# Bus.net
KiCad netlist of a schematic drawn in Altium Designer
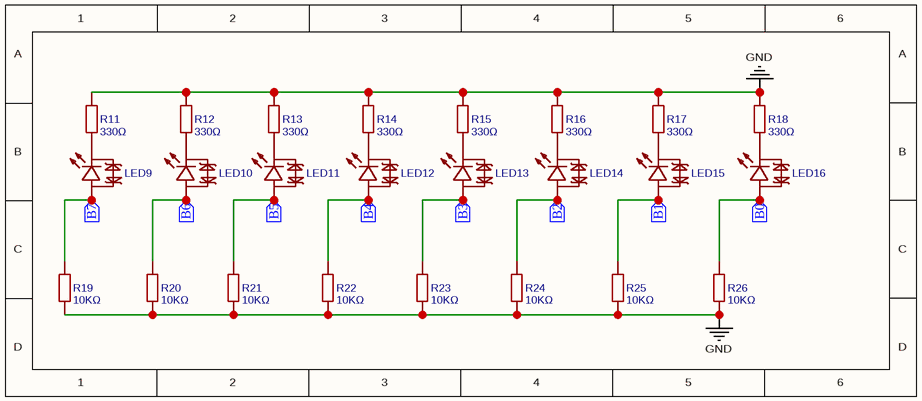
[diagram p0: Bus.schdoc]

(export (version "E")
  (design (tool "Eeschema 10.0.6"))
  (components
    (comp (ref "LED9")
      (value "204-15UTC/S400-X9-L")
      (fields (field (name "MANUFACTURER") "EVERLIGHT(亿光)") (field (name "CONTRIBUTOR") "LCSC"))
      (libsource (lib "altium-import") (part "root_1_204-15UTC/S400-X9-L_"))
    )
    (comp (ref "LED10")
      (value "204-15UTC/S400-X9-L")
      (fields (field (name "MANUFACTURER") "EVERLIGHT(亿光)") (field (name "CONTRIBUTOR") "LCSC"))
      (libsource (lib "altium-import") (part "root_1_204-15UTC/S400-X9-L_"))
    )
    (comp (ref "LED11")
      (value "204-15UTC/S400-X9-L")
      (fields (field (name "MANUFACTURER") "EVERLIGHT(亿光)") (field (name "CONTRIBUTOR") "LCSC"))
      (libsource (lib "altium-import") (part "root_1_204-15UTC/S400-X9-L_"))
    )
    (comp (ref "LED12")
      (value "204-15UTC/S400-X9-L")
      (fields (field (name "MANUFACTURER") "EVERLIGHT(亿光)") (field (name "CONTRIBUTOR") "LCSC"))
      (libsource (lib "altium-import") (part "root_1_204-15UTC/S400-X9-L_"))
    )
    (comp (ref "LED13")
      (value "204-15UTC/S400-X9-L")
      (fields (field (name "MANUFACTURER") "EVERLIGHT(亿光)") (field (name "CONTRIBUTOR") "LCSC"))
      (libsource (lib "altium-import") (part "root_1_204-15UTC/S400-X9-L_"))
    )
    (comp (ref "LED14")
      (value "204-15UTC/S400-X9-L")
      (fields (field (name "MANUFACTURER") "EVERLIGHT(亿光)") (field (name "CONTRIBUTOR") "LCSC"))
      (libsource (lib "altium-import") (part "root_1_204-15UTC/S400-X9-L_"))
    )
    (comp (ref "LED15")
      (value "204-15UTC/S400-X9-L")
      (fields (field (name "MANUFACTURER") "EVERLIGHT(亿光)") (field (name "CONTRIBUTOR") "LCSC"))
      (libsource (lib "altium-import") (part "root_1_204-15UTC/S400-X9-L_"))
    )
    (comp (ref "LED16")
      (value "204-15UTC/S400-X9-L")
      (fields (field (name "MANUFACTURER") "EVERLIGHT(亿光)") (field (name "CONTRIBUTOR") "LCSC"))
      (libsource (lib "altium-import") (part "root_1_204-15UTC/S400-X9-L_"))
    )
    (comp (ref "R11")
      (value "330Ω")
      (fields
        (field (name "MANUFACTURER") "CCO(千志电子)")
        (field (name "MANUFACTURER PART") "MF1/2W-0.1Ω±1% T")
        (field (name "CONTRIBUTOR") "LCSC")
      )
      (libsource (lib "altium-import") (part "root_1_330Ω_"))
    )
    (comp (ref "R12")
      (value "330Ω")
      (fields
        (field (name "MANUFACTURER") "CCO(千志电子)")
        (field (name "MANUFACTURER PART") "MF1/2W-0.1Ω±1% T")
        (field (name "CONTRIBUTOR") "LCSC")
      )
      (libsource (lib "altium-import") (part "root_1_330Ω_"))
    )
    (comp (ref "R13")
      (value "330Ω")
      (fields
        (field (name "MANUFACTURER") "CCO(千志电子)")
        (field (name "MANUFACTURER PART") "MF1/2W-0.1Ω±1% T")
        (field (name "CONTRIBUTOR") "LCSC")
      )
      (libsource (lib "altium-import") (part "root_1_330Ω_"))
    )
    (comp (ref "R14")
      (value "330Ω")
      (fields
        (field (name "MANUFACTURER") "CCO(千志电子)")
        (field (name "MANUFACTURER PART") "MF1/2W-0.1Ω±1% T")
        (field (name "CONTRIBUTOR") "LCSC")
      )
      (libsource (lib "altium-import") (part "root_1_330Ω_"))
    )
    (comp (ref "R15")
      (value "330Ω")
      (fields
        (field (name "MANUFACTURER") "CCO(千志电子)")
        (field (name "MANUFACTURER PART") "MF1/2W-0.1Ω±1% T")
        (field (name "CONTRIBUTOR") "LCSC")
      )
      (libsource (lib "altium-import") (part "root_1_330Ω_"))
    )
    (comp (ref "R16")
      (value "330Ω")
      (fields
        (field (name "MANUFACTURER") "CCO(千志电子)")
        (field (name "MANUFACTURER PART") "MF1/2W-0.1Ω±1% T")
        (field (name "CONTRIBUTOR") "LCSC")
      )
      (libsource (lib "altium-import") (part "root_1_330Ω_"))
    )
    (comp (ref "R17")
      (value "330Ω")
      (fields
        (field (name "MANUFACTURER") "CCO(千志电子)")
        (field (name "MANUFACTURER PART") "MF1/2W-0.1Ω±1% T")
        (field (name "CONTRIBUTOR") "LCSC")
      )
      (libsource (lib "altium-import") (part "root_1_330Ω_"))
    )
    (comp (ref "R18")
      (value "330Ω")
      (fields
        (field (name "MANUFACTURER") "CCO(千志电子)")
        (field (name "MANUFACTURER PART") "MF1/2W-0.1Ω±1% T")
        (field (name "CONTRIBUTOR") "LCSC")
      )
      (libsource (lib "altium-import") (part "root_1_330Ω_"))
    )
    (comp (ref "R19")
      (value "10KΩ")
      (fields
        (field (name "MANUFACTURER") "CCO(千志电子)")
        (field (name "MANUFACTURER PART") "MF1/2W-0.1Ω±1% T")
        (field (name "CONTRIBUTOR") "LCSC")
      )
      (libsource (lib "altium-import") (part "root_1_10KΩ_"))
    )
    (comp (ref "R20")
      (value "10KΩ")
      (fields
        (field (name "MANUFACTURER") "CCO(千志电子)")
        (field (name "MANUFACTURER PART") "MF1/2W-0.1Ω±1% T")
        (field (name "CONTRIBUTOR") "LCSC")
      )
      (libsource (lib "altium-import") (part "root_1_10KΩ_"))
    )
    (comp (ref "R21")
      (value "10KΩ")
      (fields
        (field (name "MANUFACTURER") "CCO(千志电子)")
        (field (name "MANUFACTURER PART") "MF1/2W-0.1Ω±1% T")
        (field (name "CONTRIBUTOR") "LCSC")
      )
      (libsource (lib "altium-import") (part "root_1_10KΩ_"))
    )
    (comp (ref "R22")
      (value "10KΩ")
      (fields
        (field (name "MANUFACTURER") "CCO(千志电子)")
        (field (name "MANUFACTURER PART") "MF1/2W-0.1Ω±1% T")
        (field (name "CONTRIBUTOR") "LCSC")
      )
      (libsource (lib "altium-import") (part "root_1_10KΩ_"))
    )
    (comp (ref "R23")
      (value "10KΩ")
      (fields
        (field (name "MANUFACTURER") "CCO(千志电子)")
        (field (name "MANUFACTURER PART") "MF1/2W-0.1Ω±1% T")
        (field (name "CONTRIBUTOR") "LCSC")
      )
      (libsource (lib "altium-import") (part "root_1_10KΩ_"))
    )
    (comp (ref "R24")
      (value "10KΩ")
      (fields
        (field (name "MANUFACTURER") "CCO(千志电子)")
        (field (name "MANUFACTURER PART") "MF1/2W-0.1Ω±1% T")
        (field (name "CONTRIBUTOR") "LCSC")
      )
      (libsource (lib "altium-import") (part "root_1_10KΩ_"))
    )
    (comp (ref "R25")
      (value "10KΩ")
      (fields
        (field (name "MANUFACTURER") "CCO(千志电子)")
        (field (name "MANUFACTURER PART") "MF1/2W-0.1Ω±1% T")
        (field (name "CONTRIBUTOR") "LCSC")
      )
      (libsource (lib "altium-import") (part "root_1_10KΩ_"))
    )
    (comp (ref "R26")
      (value "10KΩ")
      (fields
        (field (name "MANUFACTURER") "CCO(千志电子)")
        (field (name "MANUFACTURER PART") "MF1/2W-0.1Ω±1% T")
        (field (name "CONTRIBUTOR") "LCSC")
      )
      (libsource (lib "altium-import") (part "root_1_10KΩ_"))
    )
  )
  (nets
    (net (code "1") (name "/B0") (class "Default")
      (node (ref "LED16") (pin "1") (pinfunction "A_1") (pintype "passive"))
      (node (ref "R26") (pin "2") (pinfunction "2_2") (pintype "passive"))
    )
    (net (code "2") (name "/B1") (class "Default")
      (node (ref "LED15") (pin "1") (pinfunction "A_1") (pintype "passive"))
      (node (ref "R25") (pin "2") (pinfunction "2_2") (pintype "passive"))
    )
    (net (code "3") (name "/B2") (class "Default")
      (node (ref "LED14") (pin "1") (pinfunction "A_1") (pintype "passive"))
      (node (ref "R24") (pin "2") (pinfunction "2_2") (pintype "passive"))
    )
    (net (code "4") (name "/B3") (class "Default")
      (node (ref "LED13") (pin "1") (pinfunction "A_1") (pintype "passive"))
      (node (ref "R23") (pin "2") (pinfunction "2_2") (pintype "passive"))
    )
    (net (code "5") (name "/B4") (class "Default")
      (node (ref "LED12") (pin "1") (pinfunction "A_1") (pintype "passive"))
      (node (ref "R22") (pin "2") (pinfunction "2_2") (pintype "passive"))
    )
    (net (code "6") (name "/B5") (class "Default")
      (node (ref "LED11") (pin "1") (pinfunction "A_1") (pintype "passive"))
      (node (ref "R21") (pin "2") (pinfunction "2_2") (pintype "passive"))
    )
    (net (code "7") (name "/B6") (class "Default")
      (node (ref "LED10") (pin "1") (pinfunction "A_1") (pintype "passive"))
      (node (ref "R20") (pin "2") (pinfunction "2_2") (pintype "passive"))
    )
    (net (code "8") (name "/B7") (class "Default")
      (node (ref "LED9") (pin "1") (pinfunction "A_1") (pintype "passive"))
      (node (ref "R19") (pin "2") (pinfunction "2_2") (pintype "passive"))
    )
    (net (code "9") (name "GND") (class "Default")
      (node (ref "R11") (pin "2") (pinfunction "2_2") (pintype "passive"))
      (node (ref "R12") (pin "2") (pinfunction "2_2") (pintype "passive"))
      (node (ref "R13") (pin "2") (pinfunction "2_2") (pintype "passive"))
      (node (ref "R14") (pin "2") (pinfunction "2_2") (pintype "passive"))
      (node (ref "R15") (pin "2") (pinfunction "2_2") (pintype "passive"))
      (node (ref "R16") (pin "2") (pinfunction "2_2") (pintype "passive"))
      (node (ref "R17") (pin "2") (pinfunction "2_2") (pintype "passive"))
      (node (ref "R18") (pin "2") (pinfunction "2_2") (pintype "passive"))
      (node (ref "R19") (pin "1") (pinfunction "1_1") (pintype "passive"))
      (node (ref "R20") (pin "1") (pinfunction "1_1") (pintype "passive"))
      (node (ref "R21") (pin "1") (pinfunction "1_1") (pintype "passive"))
      (node (ref "R22") (pin "1") (pinfunction "1_1") (pintype "passive"))
      (node (ref "R23") (pin "1") (pinfunction "1_1") (pintype "passive"))
      (node (ref "R24") (pin "1") (pinfunction "1_1") (pintype "passive"))
      (node (ref "R25") (pin "1") (pinfunction "1_1") (pintype "passive"))
      (node (ref "R26") (pin "1") (pinfunction "1_1") (pintype "passive"))
    )
    (net (code "10") (name "Net-(LED9-C)") (class "Default")
      (node (ref "LED9") (pin "2") (pinfunction "C_2") (pintype "passive"))
      (node (ref "R11") (pin "1") (pinfunction "1_1") (pintype "passive"))
    )
    (net (code "11") (name "Net-(LED10-C)") (class "Default")
      (node (ref "LED10") (pin "2") (pinfunction "C_2") (pintype "passive"))
      (node (ref "R12") (pin "1") (pinfunction "1_1") (pintype "passive"))
    )
    (net (code "12") (name "Net-(LED11-C)") (class "Default")
      (node (ref "LED11") (pin "2") (pinfunction "C_2") (pintype "passive"))
      (node (ref "R13") (pin "1") (pinfunction "1_1") (pintype "passive"))
    )
    (net (code "13") (name "Net-(LED12-C)") (class "Default")
      (node (ref "LED12") (pin "2") (pinfunction "C_2") (pintype "passive"))
      (node (ref "R14") (pin "1") (pinfunction "1_1") (pintype "passive"))
    )
    (net (code "14") (name "Net-(LED13-C)") (class "Default")
      (node (ref "LED13") (pin "2") (pinfunction "C_2") (pintype "passive"))
      (node (ref "R15") (pin "1") (pinfunction "1_1") (pintype "passive"))
    )
    (net (code "15") (name "Net-(LED14-C)") (class "Default")
      (node (ref "LED14") (pin "2") (pinfunction "C_2") (pintype "passive"))
      (node (ref "R16") (pin "1") (pinfunction "1_1") (pintype "passive"))
    )
    (net (code "16") (name "Net-(LED15-C)") (class "Default")
      (node (ref "LED15") (pin "2") (pinfunction "C_2") (pintype "passive"))
      (node (ref "R17") (pin "1") (pinfunction "1_1") (pintype "passive"))
    )
    (net (code "17") (name "Net-(LED16-C)") (class "Default")
      (node (ref "LED16") (pin "2") (pinfunction "C_2") (pintype "passive"))
      (node (ref "R18") (pin "1") (pinfunction "1_1") (pintype "passive"))
    )
  )
)
